# stacja_prototyp.net
KiCad netlist of a schematic drawn in EAGLE
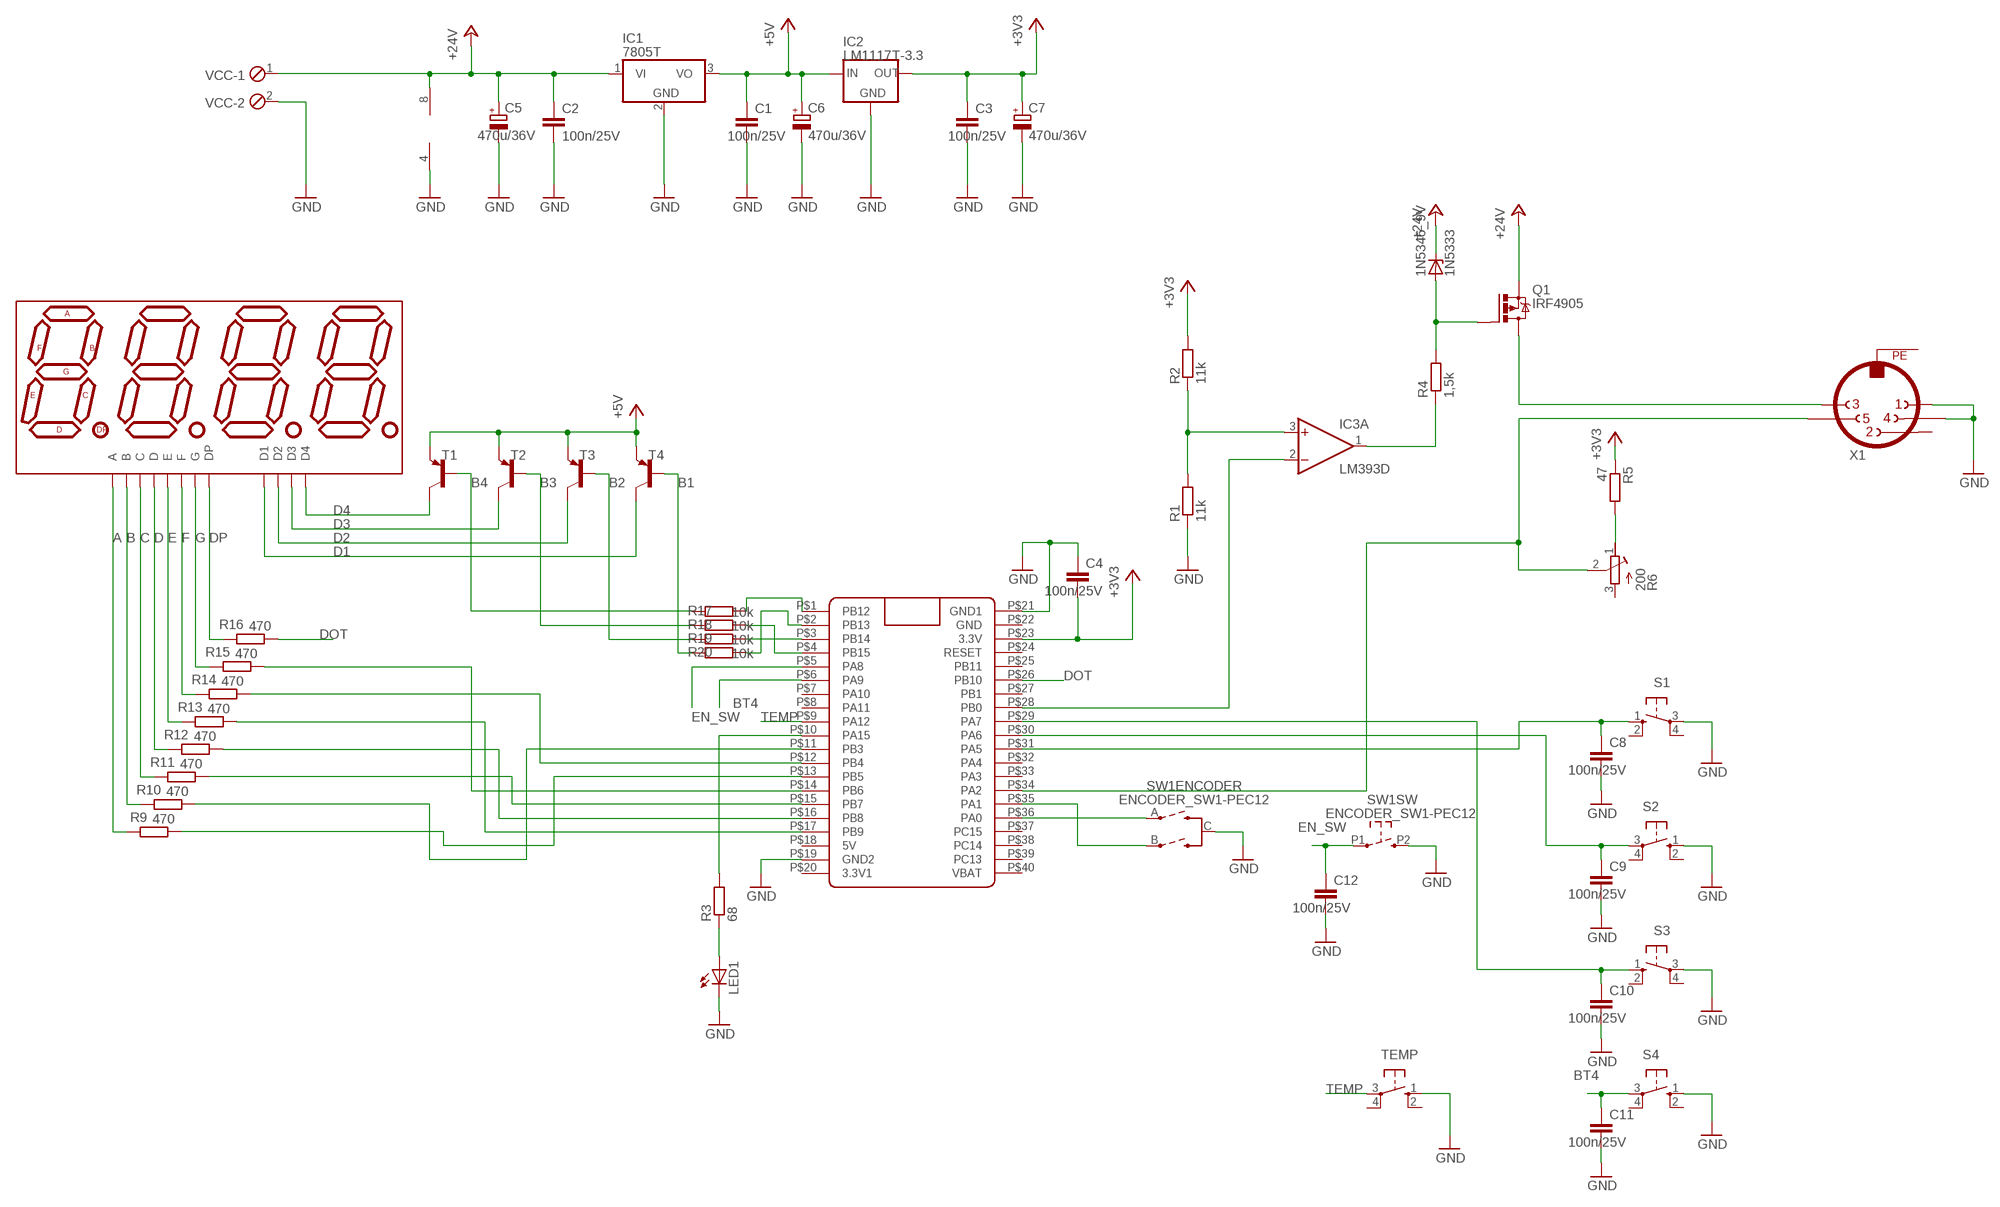
[diagram p0: schematic, sheet 1]

(export (version "E")
  (design (tool "Eeschema 10.0.6"))
  (components
    (comp (ref "1N5346_9V")
      (value "1N5333")
      (footprint "eagle-import:C1702-15")
      (libsource (lib "eagle-import") (part "1N5333"))
    )
    (comp (ref "C1")
      (value "100n/25V")
      (footprint "eagle-import:C1206")
      (libsource (lib "eagle-import") (part "C-EUC1206"))
    )
    (comp (ref "C2")
      (value "100n/25V")
      (footprint "eagle-import:C1206")
      (libsource (lib "eagle-import") (part "C-EUC1206"))
    )
    (comp (ref "C3")
      (value "100n/25V")
      (footprint "eagle-import:C1206")
      (libsource (lib "eagle-import") (part "C-EUC1206"))
    )
    (comp (ref "C4")
      (value "100n/25V")
      (footprint "eagle-import:C1206")
      (libsource (lib "eagle-import") (part "C-EUC1206"))
    )
    (comp (ref "C5")
      (value "470u/36V")
      (footprint "eagle-import:E2,5-5")
      (libsource (lib "eagle-import") (part "CPOL-EUE2.5-5"))
    )
    (comp (ref "C6")
      (value "470u/36V")
      (footprint "eagle-import:E2,5-5")
      (libsource (lib "eagle-import") (part "CPOL-EUE2.5-5"))
    )
    (comp (ref "C7")
      (value "470u/36V")
      (footprint "eagle-import:E2,5-5")
      (libsource (lib "eagle-import") (part "CPOL-EUE2.5-5"))
    )
    (comp (ref "C8")
      (value "100n/25V")
      (footprint "eagle-import:C1206")
      (libsource (lib "eagle-import") (part "C-EUC1206"))
    )
    (comp (ref "C9")
      (value "100n/25V")
      (footprint "eagle-import:C1206")
      (libsource (lib "eagle-import") (part "C-EUC1206"))
    )
    (comp (ref "C10")
      (value "100n/25V")
      (footprint "eagle-import:C1206")
      (libsource (lib "eagle-import") (part "C-EUC1206"))
    )
    (comp (ref "C11")
      (value "100n/25V")
      (footprint "eagle-import:C1206")
      (libsource (lib "eagle-import") (part "C-EUC1206"))
    )
    (comp (ref "C12")
      (value "100n/25V")
      (footprint "eagle-import:C1206")
      (libsource (lib "eagle-import") (part "C-EUC1206"))
    )
    (comp (ref "DISP1")
      (value "ATA8041ARBJ")
      (footprint "eagle-import:7-SEGMENT-4DIGIT-20MM")
      (libsource (lib "eagle-import") (part "7-SEGMENT-4DIGIT-20MM-RED"))
    )
    (comp (ref "IC1")
      (value "7805T")
      (footprint "eagle-import:TO220H")
      (libsource (lib "eagle-import") (part "78T05"))
    )
    (comp (ref "IC2")
      (value "LM1117T-3.3")
      (footprint "eagle-import:TO220")
      (libsource (lib "eagle-import") (part "LM1117T-3.3"))
    )
    (comp (ref "IC3")
      (value "LM393D")
      (footprint "eagle-import:SO08")
      (libsource (lib "eagle-import") (part "LM393D"))
    )
    (comp (ref "LED1")
      (value "LED5MM")
      (footprint "eagle-import:LED5MM")
      (libsource (lib "eagle-import") (part "LED5MM"))
    )
    (comp (ref "Q1")
      (value "IRF4905")
      (footprint "eagle-import:TO220BH")
      (libsource (lib "eagle-import") (part "IRF4905"))
    )
    (comp (ref "R1")
      (value "11k")
      (footprint "eagle-import:R0805")
      (libsource (lib "eagle-import") (part "R-EU_R0805"))
    )
    (comp (ref "R2")
      (value "11k")
      (footprint "eagle-import:R0805")
      (libsource (lib "eagle-import") (part "R-EU_R0805"))
    )
    (comp (ref "R3")
      (value "68")
      (footprint "eagle-import:R0805")
      (libsource (lib "eagle-import") (part "R-EU_R0805"))
    )
    (comp (ref "R4")
      (value "1,5k")
      (footprint "eagle-import:0207_15")
      (libsource (lib "eagle-import") (part "R-EU_0207/15"))
    )
    (comp (ref "R5")
      (value "47")
      (footprint "eagle-import:0207_15")
      (libsource (lib "eagle-import") (part "R-EU_0207/15"))
    )
    (comp (ref "R6")
      (value "200")
      (footprint "eagle-import:RTRIM43P")
      (libsource (lib "eagle-import") (part "R-TRIMM43P"))
    )
    (comp (ref "R9")
      (value "470")
      (footprint "eagle-import:M0805")
      (libsource (lib "eagle-import") (part "R-EU_M0805"))
    )
    (comp (ref "R10")
      (value "470")
      (footprint "eagle-import:M0805")
      (libsource (lib "eagle-import") (part "R-EU_M0805"))
    )
    (comp (ref "R11")
      (value "470")
      (footprint "eagle-import:M0805")
      (libsource (lib "eagle-import") (part "R-EU_M0805"))
    )
    (comp (ref "R12")
      (value "470")
      (footprint "eagle-import:M0805")
      (libsource (lib "eagle-import") (part "R-EU_M0805"))
    )
    (comp (ref "R13")
      (value "470")
      (footprint "eagle-import:M0805")
      (libsource (lib "eagle-import") (part "R-EU_M0805"))
    )
    (comp (ref "R14")
      (value "470")
      (footprint "eagle-import:M0805")
      (libsource (lib "eagle-import") (part "R-EU_M0805"))
    )
    (comp (ref "R15")
      (value "470")
      (footprint "eagle-import:M0805")
      (libsource (lib "eagle-import") (part "R-EU_M0805"))
    )
    (comp (ref "R16")
      (value "470")
      (footprint "eagle-import:M0805")
      (libsource (lib "eagle-import") (part "R-EU_M0805"))
    )
    (comp (ref "R17")
      (value "10k")
      (footprint "eagle-import:M0805")
      (libsource (lib "eagle-import") (part "R-EU_M0805"))
    )
    (comp (ref "R18")
      (value "10k")
      (footprint "eagle-import:M0805")
      (libsource (lib "eagle-import") (part "R-EU_M0805"))
    )
    (comp (ref "R19")
      (value "10k")
      (footprint "eagle-import:M0805")
      (libsource (lib "eagle-import") (part "R-EU_M0805"))
    )
    (comp (ref "R20")
      (value "10k")
      (footprint "eagle-import:M0805")
      (libsource (lib "eagle-import") (part "R-EU_M0805"))
    )
    (comp (ref "S1")
      (value "10-XX")
      (footprint "eagle-import:B3F-10XX")
      (fields (field (name "MPN") "B3F-1000"))
      (libsource (lib "eagle-import") (part "10-XX"))
    )
    (comp (ref "S2")
      (value "10-XX")
      (footprint "eagle-import:B3F-10XX")
      (fields (field (name "MPN") "B3F-1000"))
      (libsource (lib "eagle-import") (part "10-XX"))
    )
    (comp (ref "S3")
      (value "10-XX")
      (footprint "eagle-import:B3F-10XX")
      (fields (field (name "MPN") "B3F-1000"))
      (libsource (lib "eagle-import") (part "10-XX"))
    )
    (comp (ref "S4")
      (value "10-XX")
      (footprint "eagle-import:B3F-10XX")
      (fields (field (name "MPN") "B3F-1000"))
      (libsource (lib "eagle-import") (part "10-XX"))
    )
    (comp (ref "SW1")
      (value "ENCODER_SW1-PEC12")
      (footprint "eagle-import:PEC12_INCREMENTAL_ENCODER")
      (libsource (lib "eagle-import") (part "ENCODER_SW1-PEC12"))
    )
    (comp (ref "T1")
      (value "BC857B-PNP-SOT23-BEC")
      (footprint "eagle-import:SOT23-BEC")
      (libsource (lib "eagle-import") (part "-PNP-SOT23-BECBC857B"))
    )
    (comp (ref "T2")
      (value "BC857B-PNP-SOT23-BEC")
      (footprint "eagle-import:SOT23-BEC")
      (libsource (lib "eagle-import") (part "-PNP-SOT23-BECBC857B"))
    )
    (comp (ref "T3")
      (value "BC857B-PNP-SOT23-BEC")
      (footprint "eagle-import:SOT23-BEC")
      (libsource (lib "eagle-import") (part "-PNP-SOT23-BECBC857B"))
    )
    (comp (ref "T4")
      (value "BC857B-PNP-SOT23-BEC")
      (footprint "eagle-import:SOT23-BEC")
      (libsource (lib "eagle-import") (part "-PNP-SOT23-BECBC857B"))
    )
    (comp (ref "TEMP")
      (value "10-XX")
      (footprint "eagle-import:B3F-10XX")
      (fields (field (name "MPN") "B3F-1000"))
      (libsource (lib "eagle-import") (part "10-XX"))
    )
    (comp (ref "U$1")
      (value "BLUE_PILL")
      (footprint "eagle-import:BLUE_PILL")
      (libsource (lib "eagle-import") (part "BLUE_PILL"))
    )
    (comp (ref "VCC")
      (value "MPT2")
      (footprint "eagle-import:2POL254")
      (libsource (lib "eagle-import") (part "MPT2"))
    )
    (comp (ref "X1")
      (value "MAB5SV")
      (footprint "eagle-import:MAB5SV")
      (libsource (lib "eagle-import") (part "MAB5SV"))
    )
  )
  (nets
    (net (code "1") (name "+3V3") (class "Default")
      (node (ref "C3") (pin "1") (pinfunction "1_1") (pintype "passive"))
      (node (ref "C4") (pin "2") (pinfunction "2_2") (pintype "passive"))
      (node (ref "C7") (pin "+") (pinfunction "+_+") (pintype "passive"))
      (node (ref "IC2") (pin "2") (pinfunction "OUT_2") (pintype "passive"))
      (node (ref "R2") (pin "2") (pinfunction "2_2") (pintype "passive"))
      (node (ref "R5") (pin "1") (pinfunction "1_1") (pintype "passive"))
      (node (ref "U$1") (pin "P$23") (pinfunction "3.3V_P$23") (pintype "bidirectional"))
    )
    (net (code "2") (name "+5V") (class "Default")
      (node (ref "C1") (pin "1") (pinfunction "1_1") (pintype "passive"))
      (node (ref "C6") (pin "+") (pinfunction "+_+") (pintype "passive"))
      (node (ref "IC1") (pin "3") (pinfunction "VO_3") (pintype "passive"))
      (node (ref "IC2") (pin "3") (pinfunction "IN_3") (pintype "input"))
      (node (ref "T1") (pin "E") (pinfunction "E_E") (pintype "passive"))
      (node (ref "T2") (pin "E") (pinfunction "E_E") (pintype "passive"))
      (node (ref "T3") (pin "E") (pinfunction "E_E") (pintype "passive"))
      (node (ref "T4") (pin "E") (pinfunction "E_E") (pintype "passive"))
    )
    (net (code "3") (name "+24V") (class "Default")
      (node (ref "1N5346_9V") (pin "C") (pinfunction "C_C") (pintype "passive"))
      (node (ref "C2") (pin "1") (pinfunction "1_1") (pintype "passive"))
      (node (ref "C5") (pin "+") (pinfunction "+_+") (pintype "passive"))
      (node (ref "IC1") (pin "1") (pinfunction "VI_1") (pintype "input"))
      (node (ref "IC3") (pin "8") (pinfunction "V+_8") (pintype "power_in"))
      (node (ref "Q1") (pin "S") (pinfunction "S_S") (pintype "passive"))
      (node (ref "VCC") (pin "1") (pinfunction "1_1") (pintype "passive"))
    )
    (net (code "4") (name "/A") (class "Default")
      (node (ref "DISP1") (pin "11") (pinfunction "A_11") (pintype "bidirectional"))
      (node (ref "R9") (pin "2") (pinfunction "2_2") (pintype "passive"))
    )
    (net (code "5") (name "/B") (class "Default")
      (node (ref "DISP1") (pin "7") (pinfunction "B_7") (pintype "bidirectional"))
      (node (ref "R10") (pin "2") (pinfunction "2_2") (pintype "passive"))
    )
    (net (code "6") (name "/B1") (class "Default")
      (node (ref "R20") (pin "2") (pinfunction "2_2") (pintype "passive"))
      (node (ref "T4") (pin "B") (pinfunction "B_B") (pintype "passive"))
    )
    (net (code "7") (name "/B2") (class "Default")
      (node (ref "R19") (pin "2") (pinfunction "2_2") (pintype "passive"))
      (node (ref "T3") (pin "B") (pinfunction "B_B") (pintype "passive"))
    )
    (net (code "8") (name "/B3") (class "Default")
      (node (ref "R18") (pin "2") (pinfunction "2_2") (pintype "passive"))
      (node (ref "T2") (pin "B") (pinfunction "B_B") (pintype "passive"))
    )
    (net (code "9") (name "/B4") (class "Default")
      (node (ref "R17") (pin "2") (pinfunction "2_2") (pintype "passive"))
      (node (ref "T1") (pin "B") (pinfunction "B_B") (pintype "passive"))
    )
    (net (code "10") (name "/BT4") (class "Default")
      (node (ref "C11") (pin "1") (pinfunction "1_1") (pintype "passive"))
      (node (ref "S4") (pin "3") (pinfunction "P_3") (pintype "passive"))
      (node (ref "U$1") (pin "P$6") (pinfunction "PA9_P$6") (pintype "bidirectional"))
    )
    (net (code "11") (name "/C") (class "Default")
      (node (ref "DISP1") (pin "4") (pinfunction "C_4") (pintype "bidirectional"))
      (node (ref "R11") (pin "2") (pinfunction "2_2") (pintype "passive"))
    )
    (net (code "12") (name "/D") (class "Default")
      (node (ref "DISP1") (pin "2") (pinfunction "D_2") (pintype "bidirectional"))
      (node (ref "R12") (pin "2") (pinfunction "2_2") (pintype "passive"))
    )
    (net (code "13") (name "/D1") (class "Default")
      (node (ref "DISP1") (pin "12") (pinfunction "D1_12") (pintype "bidirectional"))
      (node (ref "T4") (pin "C") (pinfunction "C_C") (pintype "passive"))
    )
    (net (code "14") (name "/D2") (class "Default")
      (node (ref "DISP1") (pin "9") (pinfunction "D2_9") (pintype "bidirectional"))
      (node (ref "T3") (pin "C") (pinfunction "C_C") (pintype "passive"))
    )
    (net (code "15") (name "/D3") (class "Default")
      (node (ref "DISP1") (pin "8") (pinfunction "D3_8") (pintype "bidirectional"))
      (node (ref "T2") (pin "C") (pinfunction "C_C") (pintype "passive"))
    )
    (net (code "16") (name "/D4") (class "Default")
      (node (ref "DISP1") (pin "6") (pinfunction "D4_6") (pintype "bidirectional"))
      (node (ref "T1") (pin "C") (pinfunction "C_C") (pintype "passive"))
    )
    (net (code "17") (name "/DOT") (class "Default")
      (node (ref "R16") (pin "1") (pinfunction "1_1") (pintype "passive"))
      (node (ref "U$1") (pin "P$26") (pinfunction "PB10_P$26") (pintype "bidirectional"))
    )
    (net (code "18") (name "/DP") (class "Default")
      (node (ref "DISP1") (pin "3") (pinfunction "DP_3") (pintype "bidirectional"))
      (node (ref "R16") (pin "2") (pinfunction "2_2") (pintype "passive"))
    )
    (net (code "19") (name "/E") (class "Default")
      (node (ref "DISP1") (pin "1") (pinfunction "E_1") (pintype "bidirectional"))
      (node (ref "R13") (pin "2") (pinfunction "2_2") (pintype "passive"))
    )
    (net (code "20") (name "/EN_SW") (class "Default")
      (node (ref "C12") (pin "1") (pinfunction "1_1") (pintype "passive"))
      (node (ref "SW1") (pin "P1") (pinfunction "1_P1") (pintype "passive"))
      (node (ref "U$1") (pin "P$5") (pinfunction "PA8_P$5") (pintype "bidirectional"))
    )
    (net (code "21") (name "/F") (class "Default")
      (node (ref "DISP1") (pin "10") (pinfunction "F_10") (pintype "bidirectional"))
      (node (ref "R14") (pin "2") (pinfunction "2_2") (pintype "passive"))
    )
    (net (code "22") (name "/G") (class "Default")
      (node (ref "DISP1") (pin "5") (pinfunction "G_5") (pintype "bidirectional"))
      (node (ref "R15") (pin "2") (pinfunction "2_2") (pintype "passive"))
    )
    (net (code "23") (name "/PE") (class "Default")
      (node (ref "X1") (pin "PE") (pinfunction "PE_PE") (pintype "power_in"))
    )
    (net (code "24") (name "/TEMP") (class "Default")
      (node (ref "TEMP") (pin "3") (pinfunction "P_3") (pintype "passive"))
      (node (ref "U$1") (pin "P$9") (pinfunction "PA12_P$9") (pintype "bidirectional"))
    )
    (net (code "25") (name "GND") (class "Default")
      (node (ref "C1") (pin "2") (pinfunction "2_2") (pintype "passive"))
      (node (ref "C10") (pin "2") (pinfunction "2_2") (pintype "passive"))
      (node (ref "C11") (pin "2") (pinfunction "2_2") (pintype "passive"))
      (node (ref "C12") (pin "2") (pinfunction "2_2") (pintype "passive"))
      (node (ref "C2") (pin "2") (pinfunction "2_2") (pintype "passive"))
      (node (ref "C3") (pin "2") (pinfunction "2_2") (pintype "passive"))
      (node (ref "C4") (pin "1") (pinfunction "1_1") (pintype "passive"))
      (node (ref "C5") (pin "-") (pinfunction "-_-") (pintype "passive"))
      (node (ref "C6") (pin "-") (pinfunction "-_-") (pintype "passive"))
      (node (ref "C7") (pin "-") (pinfunction "-_-") (pintype "passive"))
      (node (ref "C8") (pin "2") (pinfunction "2_2") (pintype "passive"))
      (node (ref "C9") (pin "2") (pinfunction "2_2") (pintype "passive"))
      (node (ref "IC1") (pin "2") (pinfunction "GND_2") (pintype "passive"))
      (node (ref "IC2") (pin "1") (pinfunction "GND_1") (pintype "input"))
      (node (ref "IC3") (pin "4") (pinfunction "V-_4") (pintype "power_in"))
      (node (ref "LED1") (pin "K") (pinfunction "C_K") (pintype "passive"))
      (node (ref "R1") (pin "1") (pinfunction "1_1") (pintype "passive"))
      (node (ref "S1") (pin "3") (pinfunction "P_3") (pintype "passive"))
      (node (ref "S2") (pin "1") (pinfunction "S_1") (pintype "passive"))
      (node (ref "S3") (pin "3") (pinfunction "P_3") (pintype "passive"))
      (node (ref "S4") (pin "1") (pinfunction "S_1") (pintype "passive"))
      (node (ref "SW1") (pin "C") (pinfunction "C_C") (pintype "passive"))
      (node (ref "SW1") (pin "P2") (pinfunction "2_P2") (pintype "passive"))
      (node (ref "TEMP") (pin "1") (pinfunction "S_1") (pintype "passive"))
      (node (ref "U$1") (pin "P$19") (pinfunction "GND2_P$19") (pintype "bidirectional"))
      (node (ref "U$1") (pin "P$21") (pinfunction "GND1_P$21") (pintype "power_in"))
      (node (ref "VCC") (pin "2") (pinfunction "1_2") (pintype "passive"))
      (node (ref "X1") (pin "1") (pinfunction "1_1") (pintype "passive"))
      (node (ref "X1") (pin "4") (pinfunction "4_4") (pintype "passive"))
    )
    (net (code "26") (name "Net-(1N5346_9V-PadA)") (class "Default")
      (node (ref "1N5346_9V") (pin "A") (pinfunction "A_A") (pintype "passive"))
      (node (ref "Q1") (pin "G") (pinfunction "G_G") (pintype "passive"))
      (node (ref "R4") (pin "2") (pinfunction "2_2") (pintype "passive"))
    )
    (net (code "27") (name "Net-(IC3A-+IN)") (class "Default")
      (node (ref "IC3") (pin "3") (pinfunction "+IN_3") (pintype "input"))
      (node (ref "R1") (pin "2") (pinfunction "2_2") (pintype "passive"))
      (node (ref "R2") (pin "1") (pinfunction "1_1") (pintype "passive"))
    )
    (net (code "28") (name "Net-(IC3A--IN)") (class "Default")
      (node (ref "IC3") (pin "2") (pinfunction "-IN_2") (pintype "input"))
      (node (ref "U$1") (pin "P$28") (pinfunction "PB0_P$28") (pintype "bidirectional"))
    )
    (net (code "29") (name "Net-(IC3A-OUT)") (class "Default")
      (node (ref "IC3") (pin "1") (pinfunction "OUT_1") (pintype "output"))
      (node (ref "R4") (pin "1") (pinfunction "1_1") (pintype "passive"))
    )
    (net (code "30") (name "Net-(LED1-PadA)") (class "Default")
      (node (ref "LED1") (pin "A") (pinfunction "A_A") (pintype "passive"))
      (node (ref "R3") (pin "1") (pinfunction "1_1") (pintype "passive"))
    )
    (net (code "31") (name "Net-(Q1-PadD)") (class "Default")
      (node (ref "Q1") (pin "D") (pinfunction "D_D") (pintype "passive"))
      (node (ref "X1") (pin "3") (pinfunction "3_3") (pintype "passive"))
    )
    (net (code "32") (name "Net-(R6-E)") (class "Default")
      (node (ref "R5") (pin "2") (pinfunction "2_2") (pintype "passive"))
      (node (ref "R6") (pin "1") (pinfunction "E_1") (pintype "passive"))
    )
    (net (code "33") (name "Net-(R6-S)") (class "Default")
      (node (ref "R6") (pin "2") (pinfunction "S_2") (pintype "passive"))
      (node (ref "U$1") (pin "P$34") (pinfunction "PA2_P$34") (pintype "bidirectional"))
      (node (ref "X1") (pin "5") (pinfunction "5_5") (pintype "passive"))
    )
    (net (code "34") (name "Net-(S1-S)") (class "Default")
      (node (ref "C8") (pin "1") (pinfunction "1_1") (pintype "passive"))
      (node (ref "S1") (pin "1") (pinfunction "S_1") (pintype "passive"))
      (node (ref "U$1") (pin "P$31") (pinfunction "PA5_P$31") (pintype "bidirectional"))
    )
    (net (code "35") (name "Net-(S2-P)") (class "Default")
      (node (ref "C9") (pin "1") (pinfunction "1_1") (pintype "passive"))
      (node (ref "S2") (pin "3") (pinfunction "P_3") (pintype "passive"))
      (node (ref "U$1") (pin "P$30") (pinfunction "PA6_P$30") (pintype "bidirectional"))
    )
    (net (code "36") (name "Net-(S3-S)") (class "Default")
      (node (ref "C10") (pin "1") (pinfunction "1_1") (pintype "passive"))
      (node (ref "S3") (pin "1") (pinfunction "S_1") (pintype "passive"))
      (node (ref "U$1") (pin "P$29") (pinfunction "PA7_P$29") (pintype "bidirectional"))
    )
    (net (code "37") (name "Net-(U$1-PA0)") (class "Default")
      (node (ref "SW1") (pin "A") (pinfunction "A_A") (pintype "passive"))
      (node (ref "U$1") (pin "P$36") (pinfunction "PA0_P$36") (pintype "bidirectional"))
    )
    (net (code "38") (name "Net-(U$1-PA1)") (class "Default")
      (node (ref "SW1") (pin "B") (pinfunction "B_B") (pintype "passive"))
      (node (ref "U$1") (pin "P$35") (pinfunction "PA1_P$35") (pintype "bidirectional"))
    )
    (net (code "39") (name "Net-(U$1-PA15)") (class "Default")
      (node (ref "R3") (pin "2") (pinfunction "2_2") (pintype "passive"))
      (node (ref "U$1") (pin "P$10") (pinfunction "PA15_P$10") (pintype "bidirectional"))
    )
    (net (code "40") (name "Net-(U$1-PB3)") (class "Default")
      (node (ref "R10") (pin "1") (pinfunction "1_1") (pintype "passive"))
      (node (ref "U$1") (pin "P$11") (pinfunction "PB3_P$11") (pintype "bidirectional"))
    )
    (net (code "41") (name "Net-(U$1-PB4)") (class "Default")
      (node (ref "R14") (pin "1") (pinfunction "1_1") (pintype "passive"))
      (node (ref "U$1") (pin "P$12") (pinfunction "PB4_P$12") (pintype "bidirectional"))
    )
    (net (code "42") (name "Net-(U$1-PB5)") (class "Default")
      (node (ref "R9") (pin "1") (pinfunction "1_1") (pintype "passive"))
      (node (ref "U$1") (pin "P$13") (pinfunction "PB5_P$13") (pintype "bidirectional"))
    )
    (net (code "43") (name "Net-(U$1-PB6)") (class "Default")
      (node (ref "R15") (pin "1") (pinfunction "1_1") (pintype "passive"))
      (node (ref "U$1") (pin "P$14") (pinfunction "PB6_P$14") (pintype "bidirectional"))
    )
    (net (code "44") (name "Net-(U$1-PB7)") (class "Default")
      (node (ref "R11") (pin "1") (pinfunction "1_1") (pintype "passive"))
      (node (ref "U$1") (pin "P$15") (pinfunction "PB7_P$15") (pintype "bidirectional"))
    )
    (net (code "45") (name "Net-(U$1-PB8)") (class "Default")
      (node (ref "R12") (pin "1") (pinfunction "1_1") (pintype "passive"))
      (node (ref "U$1") (pin "P$16") (pinfunction "PB8_P$16") (pintype "bidirectional"))
    )
    (net (code "46") (name "Net-(U$1-PB9)") (class "Default")
      (node (ref "R13") (pin "1") (pinfunction "1_1") (pintype "passive"))
      (node (ref "U$1") (pin "P$17") (pinfunction "PB9_P$17") (pintype "bidirectional"))
    )
    (net (code "47") (name "Net-(U$1-PB12)") (class "Default")
      (node (ref "R17") (pin "1") (pinfunction "1_1") (pintype "passive"))
      (node (ref "U$1") (pin "P$1") (pinfunction "PB12_P$1") (pintype "bidirectional"))
    )
    (net (code "48") (name "Net-(U$1-PB13)") (class "Default")
      (node (ref "R20") (pin "1") (pinfunction "1_1") (pintype "passive"))
      (node (ref "U$1") (pin "P$2") (pinfunction "PB13_P$2") (pintype "bidirectional"))
    )
    (net (code "49") (name "Net-(U$1-PB14)") (class "Default")
      (node (ref "R19") (pin "1") (pinfunction "1_1") (pintype "passive"))
      (node (ref "U$1") (pin "P$3") (pinfunction "PB14_P$3") (pintype "bidirectional"))
    )
    (net (code "50") (name "Net-(U$1-PB15)") (class "Default")
      (node (ref "R18") (pin "1") (pinfunction "1_1") (pintype "passive"))
      (node (ref "U$1") (pin "P$4") (pinfunction "PB15_P$4") (pintype "bidirectional"))
    )
    (net (code "51") (name "unconnected-(R6-A-Pad3)") (class "Default")
      (node (ref "R6") (pin "3") (pinfunction "A_3") (pintype "passive"))
    )
    (net (code "52") (name "unconnected-(S1-P1-Pad4)") (class "Default")
      (node (ref "S1") (pin "4") (pinfunction "P1_4") (pintype "passive"))
    )
    (net (code "53") (name "unconnected-(S1-S1-Pad2)") (class "Default")
      (node (ref "S1") (pin "2") (pinfunction "S1_2") (pintype "passive"))
    )
    (net (code "54") (name "unconnected-(S2-P1-Pad4)") (class "Default")
      (node (ref "S2") (pin "4") (pinfunction "P1_4") (pintype "passive"))
    )
    (net (code "55") (name "unconnected-(S2-S1-Pad2)") (class "Default")
      (node (ref "S2") (pin "2") (pinfunction "S1_2") (pintype "passive"))
    )
    (net (code "56") (name "unconnected-(S3-P1-Pad4)") (class "Default")
      (node (ref "S3") (pin "4") (pinfunction "P1_4") (pintype "passive"))
    )
    (net (code "57") (name "unconnected-(S3-S1-Pad2)") (class "Default")
      (node (ref "S3") (pin "2") (pinfunction "S1_2") (pintype "passive"))
    )
    (net (code "58") (name "unconnected-(S4-P1-Pad4)") (class "Default")
      (node (ref "S4") (pin "4") (pinfunction "P1_4") (pintype "passive"))
    )
    (net (code "59") (name "unconnected-(S4-S1-Pad2)") (class "Default")
      (node (ref "S4") (pin "2") (pinfunction "S1_2") (pintype "passive"))
    )
    (net (code "60") (name "unconnected-(TEMP-P1-Pad4)") (class "Default")
      (node (ref "TEMP") (pin "4") (pinfunction "P1_4") (pintype "passive"))
    )
    (net (code "61") (name "unconnected-(TEMP-S1-Pad2)") (class "Default")
      (node (ref "TEMP") (pin "2") (pinfunction "S1_2") (pintype "passive"))
    )
    (net (code "62") (name "unconnected-(U$1-3.3V1-PadP$20)") (class "Default")
      (node (ref "U$1") (pin "P$20") (pinfunction "3.3V1_P$20") (pintype "bidirectional"))
    )
    (net (code "63") (name "unconnected-(U$1-5V-PadP$18)") (class "Default")
      (node (ref "U$1") (pin "P$18") (pinfunction "5V_P$18") (pintype "bidirectional"))
    )
    (net (code "64") (name "unconnected-(U$1-GND-PadP$22)") (class "Default")
      (node (ref "U$1") (pin "P$22") (pinfunction "GND_P$22") (pintype "bidirectional"))
    )
    (net (code "65") (name "unconnected-(U$1-PA3-PadP$33)") (class "Default")
      (node (ref "U$1") (pin "P$33") (pinfunction "PA3_P$33") (pintype "bidirectional"))
    )
    (net (code "66") (name "unconnected-(U$1-PA4-PadP$32)") (class "Default")
      (node (ref "U$1") (pin "P$32") (pinfunction "PA4_P$32") (pintype "bidirectional"))
    )
    (net (code "67") (name "unconnected-(U$1-PA10-PadP$7)") (class "Default")
      (node (ref "U$1") (pin "P$7") (pinfunction "PA10_P$7") (pintype "bidirectional"))
    )
    (net (code "68") (name "unconnected-(U$1-PA11-PadP$8)") (class "Default")
      (node (ref "U$1") (pin "P$8") (pinfunction "PA11_P$8") (pintype "bidirectional"))
    )
    (net (code "69") (name "unconnected-(U$1-PB1-PadP$27)") (class "Default")
      (node (ref "U$1") (pin "P$27") (pinfunction "PB1_P$27") (pintype "bidirectional"))
    )
    (net (code "70") (name "unconnected-(U$1-PB11-PadP$25)") (class "Default")
      (node (ref "U$1") (pin "P$25") (pinfunction "PB11_P$25") (pintype "bidirectional"))
    )
    (net (code "71") (name "unconnected-(U$1-PC13-PadP$39)") (class "Default")
      (node (ref "U$1") (pin "P$39") (pinfunction "PC13_P$39") (pintype "bidirectional"))
    )
    (net (code "72") (name "unconnected-(U$1-PC14-PadP$38)") (class "Default")
      (node (ref "U$1") (pin "P$38") (pinfunction "PC14_P$38") (pintype "bidirectional"))
    )
    (net (code "73") (name "unconnected-(U$1-PC15-PadP$37)") (class "Default")
      (node (ref "U$1") (pin "P$37") (pinfunction "PC15_P$37") (pintype "bidirectional"))
    )
    (net (code "74") (name "unconnected-(U$1-RESET-PadP$24)") (class "Default")
      (node (ref "U$1") (pin "P$24") (pinfunction "RESET_P$24") (pintype "bidirectional"))
    )
    (net (code "75") (name "unconnected-(U$1-VBAT-PadP$40)") (class "Default")
      (node (ref "U$1") (pin "P$40") (pinfunction "VBAT_P$40") (pintype "bidirectional"))
    )
    (net (code "76") (name "unconnected-(X1-Pad2)") (class "Default")
      (node (ref "X1") (pin "2") (pinfunction "2_2") (pintype "passive"))
    )
  )
)
